# Mouse_Receive_SCH.net
KiCad netlist of a schematic drawn in Altium Designer
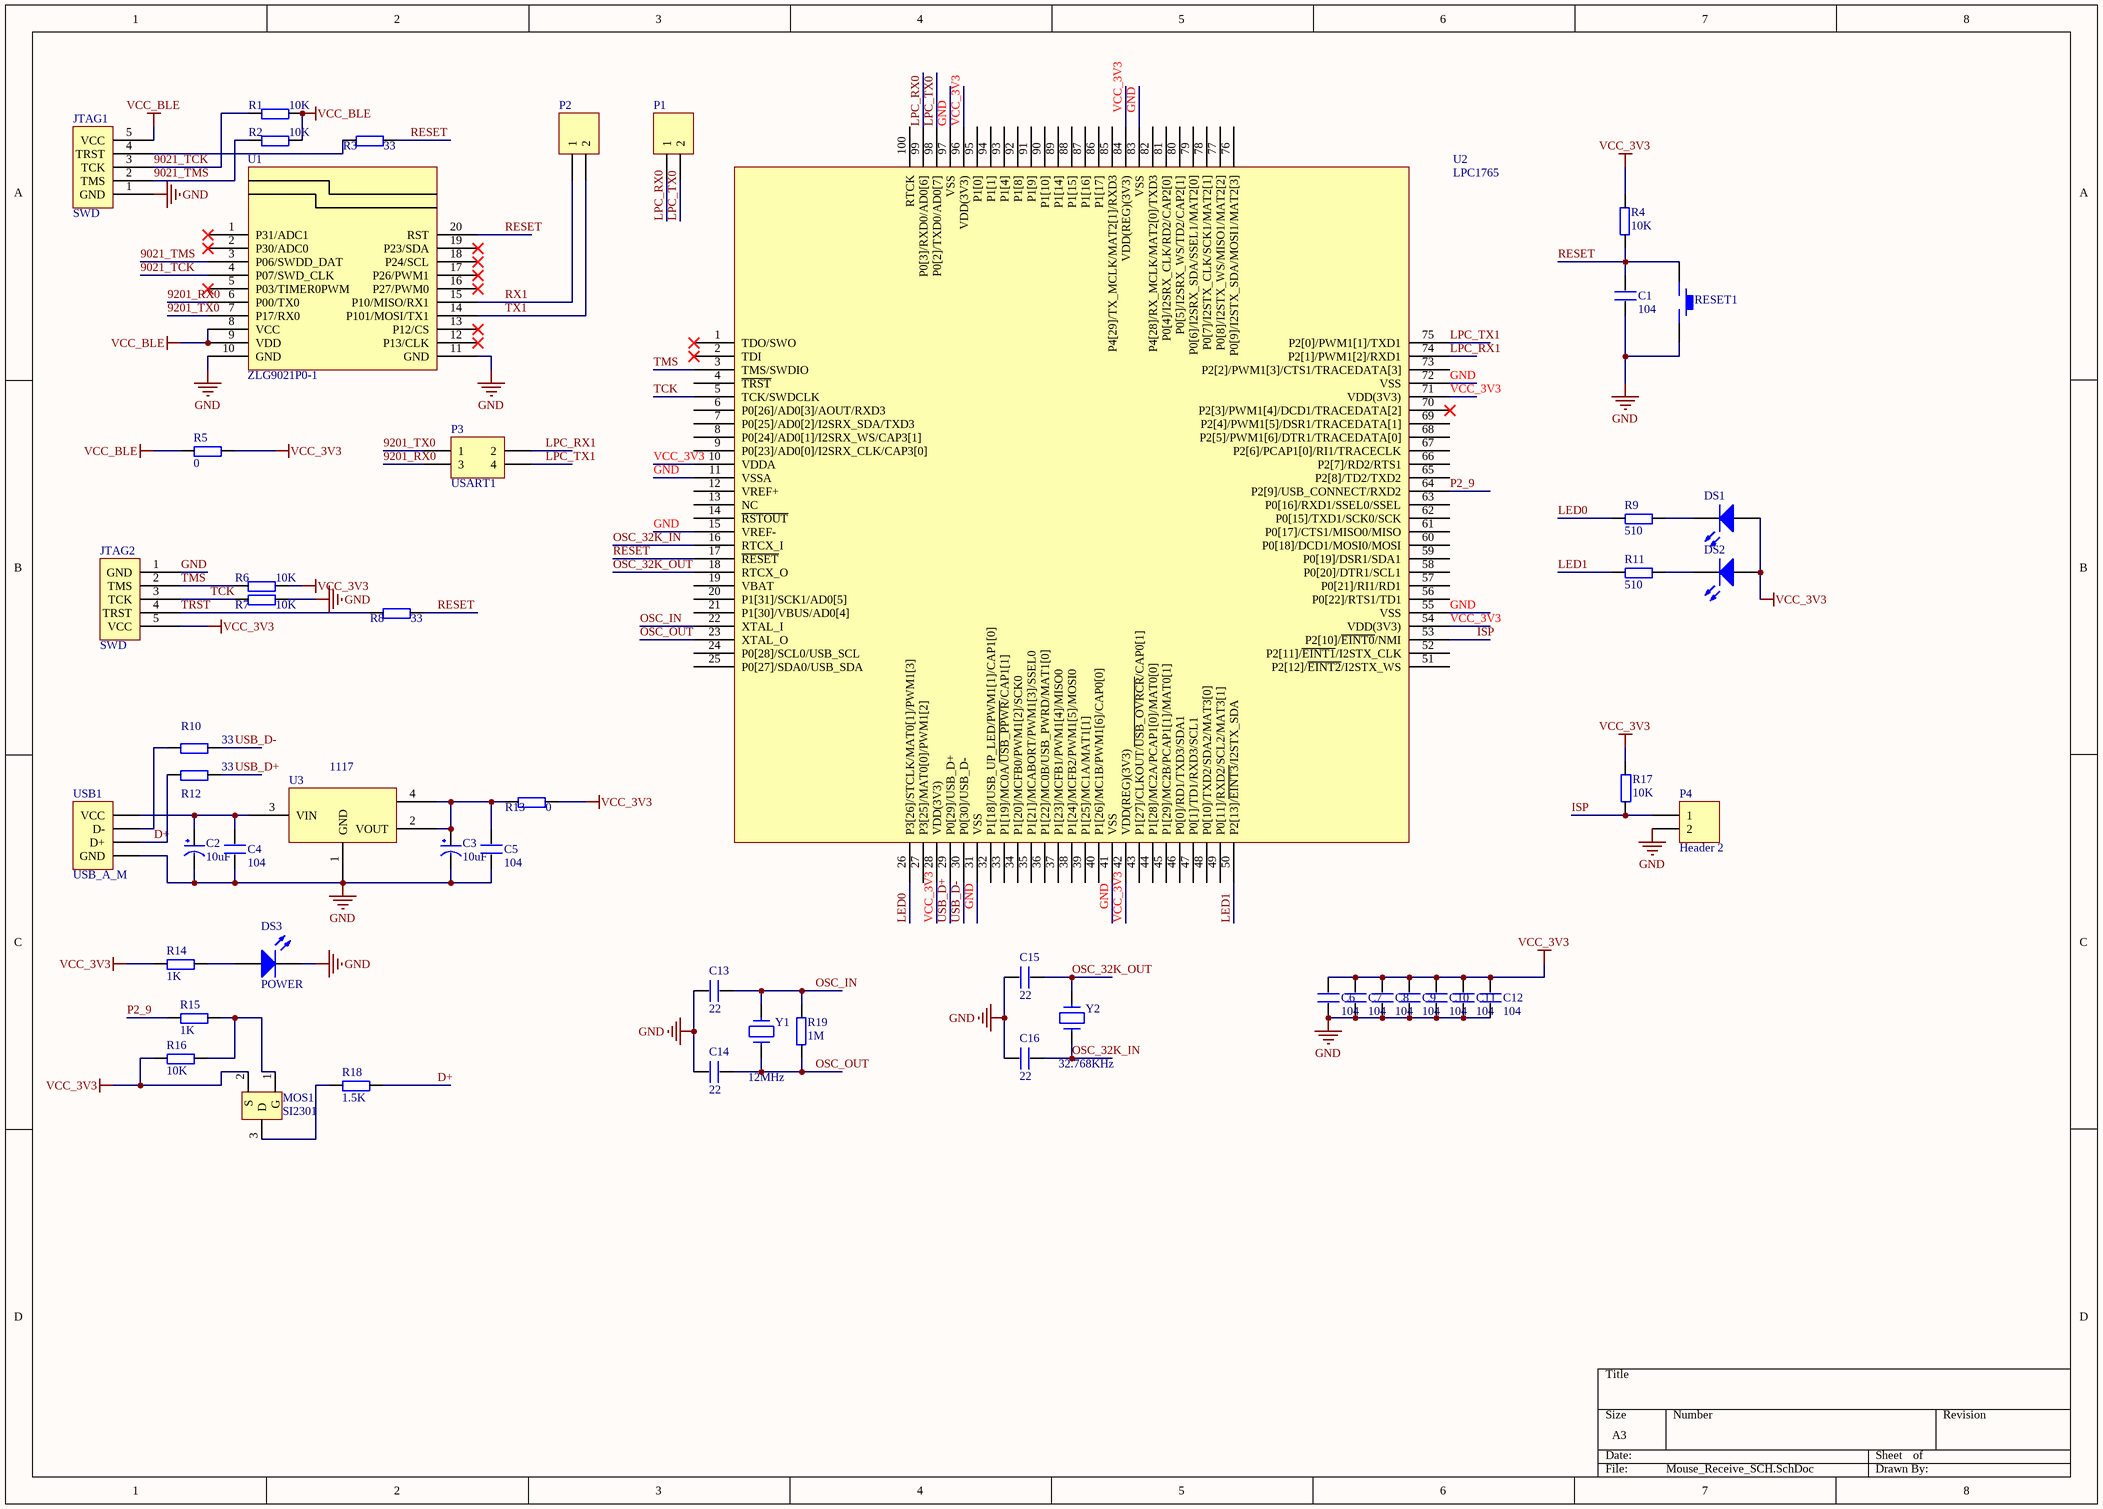
[diagram p0: Mouse_Receive_SCH.SchDoc]

(export (version "E")
  (design (tool "Eeschema 10.0.6"))
  (components
    (comp (ref "C1") (value "104") (footprint "0603P") (libsource (lib "MY_SCH_Lib") (part "C")))
    (comp (ref "C2") (value "10uF") (footprint "TAJ_A") (libsource (lib "MY_SCH_Lib") (part "CAP")))
    (comp (ref "C3") (value "10uF") (footprint "TAJ_A") (libsource (lib "MY_SCH_Lib") (part "CAP")))
    (comp (ref "C4") (value "104") (footprint "0603P") (libsource (lib "MY_SCH_Lib") (part "C")))
    (comp (ref "C5") (value "104") (footprint "0603P") (libsource (lib "MY_SCH_Lib") (part "C")))
    (comp (ref "C6") (value "104") (footprint "0603P") (libsource (lib "MY_SCH_Lib") (part "C")))
    (comp (ref "C7") (value "104") (footprint "0603P") (libsource (lib "MY_SCH_Lib") (part "C")))
    (comp (ref "C8") (value "104") (footprint "0603P") (libsource (lib "MY_SCH_Lib") (part "C")))
    (comp (ref "C9") (value "104") (footprint "0603P") (libsource (lib "MY_SCH_Lib") (part "C")))
    (comp (ref "C10") (value "104") (footprint "0603P") (libsource (lib "MY_SCH_Lib") (part "C")))
    (comp (ref "C11") (value "104") (footprint "0603P") (libsource (lib "MY_SCH_Lib") (part "C")))
    (comp (ref "C12") (value "104") (footprint "0603P") (libsource (lib "MY_SCH_Lib") (part "C")))
    (comp (ref "C13") (value "22") (footprint "0603P") (libsource (lib "MY_SCH_Lib") (part "C")))
    (comp (ref "C14") (value "22") (footprint "0603P") (libsource (lib "MY_SCH_Lib") (part "C")))
    (comp (ref "C15") (value "22") (footprint "0603P") (libsource (lib "MY_SCH_Lib") (part "C")))
    (comp (ref "C16") (value "22") (footprint "0603P") (libsource (lib "MY_SCH_Lib") (part "C")))
    (comp (ref "DS1")
      (value "~")
      (footprint "SMDLED")
      (description "Typical RED, GREEN, YELLOW, AMBER GaAs LED")
      (fields (field (name "PUBLISHER") "Altium Limited"))
      (libsource (lib "MY_SCH_Lib") (part "LED2"))
    )
    (comp (ref "DS2")
      (value "~")
      (footprint "SMDLED")
      (description "Typical RED, GREEN, YELLOW, AMBER GaAs LED")
      (fields (field (name "PUBLISHER") "Altium Limited"))
      (libsource (lib "MY_SCH_Lib") (part "LED2"))
    )
    (comp (ref "DS3")
      (value "POWER")
      (footprint "SMDLED")
      (description "Typical RED, GREEN, YELLOW, AMBER GaAs LED")
      (fields (field (name "PUBLISHER") "Altium Limited"))
      (libsource (lib "MY_SCH_Lib") (part "LED2"))
    )
    (comp (ref "JTAG1") (value "SWD") (footprint "HEAD5") (libsource (lib "") (part "SWD_1")))
    (comp (ref "JTAG2") (value "SWD") (footprint "HEAD5") (libsource (lib "MY_SCH_Lib") (part "SWD")))
    (comp (ref "MOS1")
      (value "SI2301")
      (footprint "SOT-23")
      (description "IRLML6401/SI2301")
      (libsource (lib "MY_SCH_Lib") (part "MOS-P"))
    )
    (comp (ref "P1")
      (value "~")
      (footprint "HDR1X2")
      (fields (field (name "PUBLISHER") "Altium Limited"))
      (libsource (lib "MY_SCH_Lib") (part "Header 2"))
    )
    (comp (ref "P2")
      (value "~")
      (footprint "HDR1X2")
      (fields (field (name "PUBLISHER") "Altium Limited"))
      (libsource (lib "MY_SCH_Lib") (part "Header 2"))
    )
    (comp (ref "P3")
      (value "USART1")
      (footprint "HDR2X2")
      (description "Header, 2-Pin, Dual row")
      (fields (field (name "PUBLISHER") "Altium Limited"))
      (libsource (lib "MY_SCH_Lib") (part "Header 2X2"))
    )
    (comp (ref "P4")
      (value "Header 2")
      (footprint "HDR1X2")
      (fields (field (name "PUBLISHER") "Altium Limited"))
      (libsource (lib "") (part "Header 2_1"))
    )
    (comp (ref "R1") (value "10K") (footprint "0603P") (libsource (lib "MY_SCH_Lib") (part "R")))
    (comp (ref "R2") (value "10K") (footprint "0603P") (libsource (lib "MY_SCH_Lib") (part "R")))
    (comp (ref "R3") (value "33") (footprint "0603P") (libsource (lib "MY_SCH_Lib") (part "R")))
    (comp (ref "R4") (value "10K") (footprint "0603P") (libsource (lib "MY_SCH_Lib") (part "R")))
    (comp (ref "R5") (value "0") (footprint "0603P") (libsource (lib "MY_SCH_Lib") (part "R")))
    (comp (ref "R6") (value "10K") (footprint "0603P") (libsource (lib "MY_SCH_Lib") (part "R")))
    (comp (ref "R7") (value "10K") (footprint "0603P") (libsource (lib "MY_SCH_Lib") (part "R")))
    (comp (ref "R8") (value "33") (footprint "0603P") (libsource (lib "MY_SCH_Lib") (part "R")))
    (comp (ref "R9") (value "510") (footprint "0603P") (libsource (lib "MY_SCH_Lib") (part "R")))
    (comp (ref "R10") (value "33") (footprint "0603P") (libsource (lib "MY_SCH_Lib") (part "R")))
    (comp (ref "R11") (value "510") (footprint "0603P") (libsource (lib "MY_SCH_Lib") (part "R")))
    (comp (ref "R12") (value "33") (footprint "0603P") (libsource (lib "MY_SCH_Lib") (part "R")))
    (comp (ref "R13") (value "0") (footprint "0603P") (libsource (lib "MY_SCH_Lib") (part "R")))
    (comp (ref "R14") (value "1K") (footprint "0603P") (libsource (lib "MY_SCH_Lib") (part "R")))
    (comp (ref "R15") (value "1K") (footprint "0603P") (libsource (lib "MY_SCH_Lib") (part "R")))
    (comp (ref "R16") (value "10K") (footprint "0603P") (libsource (lib "MY_SCH_Lib") (part "R")))
    (comp (ref "R17") (value "10K") (footprint "0603P") (libsource (lib "MY_SCH_Lib") (part "R")))
    (comp (ref "R18") (value "1.5K") (footprint "0603P") (libsource (lib "MY_SCH_Lib") (part "R")))
    (comp (ref "R19") (value "1M") (footprint "0603P") (libsource (lib "MY_SCH_Lib") (part "R")))
    (comp (ref "RESET1") (value "KEY_M") (footprint "KEY2") (libsource (lib "MY_SCH_Lib") (part "KEY_M")))
    (comp (ref "U1")
      (value "ZLG9021P0-1")
      (footprint "ZLG9021P0-1")
      (libsource (lib "MY_SCH_Lib") (part "ZLG9021P0-1"))
    )
    (comp (ref "U2")
      (value "LPC1765")
      (footprint "TQFP-100")
      (libsource (lib "LPC17xx_System_Sch_AD") (part "LPC1765"))
    )
    (comp (ref "U3") (value "1117") (footprint "AMS1117") (libsource (lib "MY_SCH_Lib") (part "1117")))
    (comp (ref "USB1")
      (value "USB_A_M")
      (footprint "USB-4-A-SMT-A")
      (libsource (lib "MY_SCH_Lib") (part "USB_A_M"))
    )
    (comp (ref "Y1")
      (value "12MHz")
      (footprint "8M")
      (description "Crystal")
      (libsource (lib "LPC17xx_System_Sch_AD") (part "CRYSTAL"))
    )
    (comp (ref "Y2")
      (value "32.768KHz")
      (footprint "CRY-32")
      (description "Crystal")
      (libsource (lib "LPC17xx_System_Sch_AD") (part "CRYSTAL"))
    )
  )
  (nets
    (net (code "1") (name "/9021_TCK") (class "Default")
      (node (ref "JTAG1") (pin "3") (pinfunction "TCK_3") (pintype "passive"))
      (node (ref "R1") (pin "1") (pintype "passive"))
      (node (ref "U1") (pin "4") (pinfunction "P07/SWD_CLK_4") (pintype "passive"))
    )
    (net (code "2") (name "/9021_TMS") (class "Default")
      (node (ref "JTAG1") (pin "2") (pinfunction "TMS_2") (pintype "passive"))
      (node (ref "R2") (pin "1") (pintype "passive"))
      (node (ref "U1") (pin "3") (pinfunction "P06/SWDD_DAT_3") (pintype "passive"))
    )
    (net (code "3") (name "/9201_RX0") (class "Default")
      (node (ref "P3") (pin "3") (pinfunction "3_3") (pintype "passive"))
      (node (ref "U1") (pin "6") (pinfunction "P00/TX0_6") (pintype "passive"))
    )
    (net (code "4") (name "/9201_TX0") (class "Default")
      (node (ref "P3") (pin "1") (pinfunction "1_1") (pintype "passive"))
      (node (ref "U1") (pin "7") (pinfunction "P17/RX0_7") (pintype "passive"))
    )
    (net (code "5") (name "/D+") (class "Default")
      (node (ref "R12") (pin "1") (pintype "passive"))
      (node (ref "R18") (pin "2") (pintype "passive"))
      (node (ref "USB1") (pin "3") (pinfunction "D+_3") (pintype "passive"))
    )
    (net (code "6") (name "/ISP") (class "Default")
      (node (ref "P4") (pin "1") (pinfunction "1_1") (pintype "passive"))
      (node (ref "R17") (pin "1") (pintype "passive"))
      (node (ref "U2") (pin "53") (pinfunction "P2[10]/~{EINT0}/NMI_53") (pintype "passive"))
    )
    (net (code "7") (name "/LED0") (class "Default")
      (node (ref "R9") (pin "1") (pintype "passive"))
      (node (ref "U2") (pin "26") (pinfunction "P3[26]/STCLK/MAT0[1]/PWM1[3]_26") (pintype "passive"))
    )
    (net (code "8") (name "/LED1") (class "Default")
      (node (ref "R11") (pin "1") (pintype "passive"))
      (node (ref "U2") (pin "50") (pinfunction "P2[13]/~{EINT3}/I2STX_SDA_50") (pintype "passive"))
    )
    (net (code "9") (name "/LPC_RX0") (class "Default")
      (node (ref "P1") (pin "1") (pinfunction "1_1") (pintype "passive"))
      (node (ref "U2") (pin "99") (pinfunction "P0[3]/RXD0/AD0[6]_99") (pintype "passive"))
    )
    (net (code "10") (name "/LPC_RX1") (class "Default")
      (node (ref "P3") (pin "2") (pinfunction "2_2") (pintype "passive"))
      (node (ref "U2") (pin "74") (pinfunction "P2[1]/PWM1[2]/RXD1_74") (pintype "passive"))
    )
    (net (code "11") (name "/LPC_TX0") (class "Default")
      (node (ref "P1") (pin "2") (pinfunction "2_2") (pintype "passive"))
      (node (ref "U2") (pin "98") (pinfunction "P0[2]/TXD0/AD0[7]_98") (pintype "passive"))
    )
    (net (code "12") (name "/LPC_TX1") (class "Default")
      (node (ref "P3") (pin "4") (pinfunction "4_4") (pintype "passive"))
      (node (ref "U2") (pin "75") (pinfunction "P2[0]/PWM1[1]/TXD1_75") (pintype "passive"))
    )
    (net (code "13") (name "/OSC_32K_IN") (class "Default")
      (node (ref "C16") (pin "2") (pintype "passive"))
      (node (ref "U2") (pin "16") (pinfunction "RTCX_I_16") (pintype "passive"))
      (node (ref "Y2") (pin "1") (pinfunction "1_1") (pintype "passive"))
    )
    (net (code "14") (name "/OSC_32K_OUT") (class "Default")
      (node (ref "C15") (pin "2") (pintype "passive"))
      (node (ref "U2") (pin "18") (pinfunction "RTCX_O_18") (pintype "passive"))
      (node (ref "Y2") (pin "2") (pinfunction "2_2") (pintype "passive"))
    )
    (net (code "15") (name "/OSC_IN") (class "Default")
      (node (ref "C13") (pin "2") (pintype "passive"))
      (node (ref "R19") (pin "1") (pintype "passive"))
      (node (ref "U2") (pin "22") (pinfunction "XTAL_I_22") (pintype "passive"))
      (node (ref "Y1") (pin "2") (pinfunction "2_2") (pintype "passive"))
    )
    (net (code "16") (name "/OSC_OUT") (class "Default")
      (node (ref "C14") (pin "2") (pintype "passive"))
      (node (ref "R19") (pin "2") (pintype "passive"))
      (node (ref "U2") (pin "23") (pinfunction "XTAL_O_23") (pintype "passive"))
      (node (ref "Y1") (pin "1") (pinfunction "1_1") (pintype "passive"))
    )
    (net (code "17") (name "/P2_9") (class "Default")
      (node (ref "R15") (pin "1") (pintype "passive"))
      (node (ref "U2") (pin "64") (pinfunction "P2[9]/USB_CONNECT/RXD2_64") (pintype "passive"))
    )
    (net (code "18") (name "/RESET") (class "Default")
      (node (ref "C1") (pin "2") (pintype "passive"))
      (node (ref "R3") (pin "2") (pintype "passive"))
      (node (ref "R4") (pin "1") (pintype "passive"))
      (node (ref "R8") (pin "2") (pintype "passive"))
      (node (ref "RESET1") (pin "2") (pinfunction "2_2") (pintype "passive"))
      (node (ref "U1") (pin "20") (pinfunction "RST_20") (pintype "passive"))
      (node (ref "U2") (pin "17") (pinfunction "~{RESET}_17") (pintype "passive"))
    )
    (net (code "19") (name "/RX1") (class "Default")
      (node (ref "P2") (pin "1") (pinfunction "1_1") (pintype "passive"))
      (node (ref "U1") (pin "15") (pinfunction "P10/MISO/RX1_15") (pintype "passive"))
    )
    (net (code "20") (name "/TCK") (class "Default")
      (node (ref "JTAG2") (pin "3") (pinfunction "TCK_3") (pintype "passive"))
      (node (ref "R7") (pin "1") (pintype "passive"))
      (node (ref "U2") (pin "5") (pinfunction "TCK/SWDCLK_5") (pintype "passive"))
    )
    (net (code "21") (name "/TMS") (class "Default")
      (node (ref "JTAG2") (pin "2") (pinfunction "TMS_2") (pintype "passive"))
      (node (ref "R6") (pin "1") (pintype "passive"))
      (node (ref "U2") (pin "3") (pinfunction "TMS/SWDIO_3") (pintype "passive"))
    )
    (net (code "22") (name "/TRST") (class "Default")
      (node (ref "JTAG2") (pin "4") (pinfunction "TRST_4") (pintype "passive"))
      (node (ref "R8") (pin "1") (pintype "passive"))
    )
    (net (code "23") (name "/TX1") (class "Default")
      (node (ref "P2") (pin "2") (pinfunction "2_2") (pintype "passive"))
      (node (ref "U1") (pin "14") (pinfunction "P101/MOSI/TX1_14") (pintype "passive"))
    )
    (net (code "24") (name "/USB_D+") (class "Default")
      (node (ref "R12") (pin "2") (pintype "passive"))
      (node (ref "U2") (pin "29") (pinfunction "P0[29]/USB_D+_29") (pintype "passive"))
    )
    (net (code "25") (name "/USB_D-") (class "Default")
      (node (ref "R10") (pin "2") (pintype "passive"))
      (node (ref "U2") (pin "30") (pinfunction "P0[30]/USB_D-_30") (pintype "passive"))
    )
    (net (code "26") (name "GND") (class "Default")
      (node (ref "C1") (pin "1") (pintype "passive"))
      (node (ref "C10") (pin "2") (pintype "passive"))
      (node (ref "C11") (pin "2") (pintype "passive"))
      (node (ref "C12") (pin "2") (pintype "passive"))
      (node (ref "C13") (pin "1") (pintype "passive"))
      (node (ref "C14") (pin "1") (pintype "passive"))
      (node (ref "C15") (pin "1") (pintype "passive"))
      (node (ref "C16") (pin "1") (pintype "passive"))
      (node (ref "C2") (pin "2") (pinfunction "GND_2") (pintype "passive"))
      (node (ref "C3") (pin "2") (pinfunction "GND_2") (pintype "passive"))
      (node (ref "C4") (pin "1") (pintype "passive"))
      (node (ref "C5") (pin "1") (pintype "passive"))
      (node (ref "C6") (pin "2") (pintype "passive"))
      (node (ref "C7") (pin "2") (pintype "passive"))
      (node (ref "C8") (pin "2") (pintype "passive"))
      (node (ref "C9") (pin "2") (pintype "passive"))
      (node (ref "DS3") (pin "2") (pinfunction "K_2") (pintype "passive"))
      (node (ref "JTAG1") (pin "1") (pinfunction "GND_1") (pintype "passive"))
      (node (ref "JTAG2") (pin "1") (pinfunction "GND_1") (pintype "passive"))
      (node (ref "P4") (pin "2") (pinfunction "2_2") (pintype "passive"))
      (node (ref "R7") (pin "2") (pintype "passive"))
      (node (ref "RESET1") (pin "1") (pinfunction "1_1") (pintype "passive"))
      (node (ref "U1") (pin "10") (pinfunction "GND_10") (pintype "passive"))
      (node (ref "U1") (pin "11") (pinfunction "GND_11") (pintype "passive"))
      (node (ref "U2") (pin "11") (pinfunction "VSSA_11") (pintype "passive"))
      (node (ref "U2") (pin "15") (pinfunction "VREF-_15") (pintype "passive"))
      (node (ref "U2") (pin "31") (pinfunction "VSS_31") (pintype "passive"))
      (node (ref "U2") (pin "41") (pinfunction "VSS_41") (pintype "passive"))
      (node (ref "U2") (pin "55") (pinfunction "VSS_55") (pintype "passive"))
      (node (ref "U2") (pin "72") (pinfunction "VSS_72") (pintype "passive"))
      (node (ref "U2") (pin "83") (pinfunction "VSS_83") (pintype "passive"))
      (node (ref "U2") (pin "97") (pinfunction "VSS_97") (pintype "passive"))
      (node (ref "U3") (pin "1") (pinfunction "GND_1") (pintype "passive"))
      (node (ref "USB1") (pin "4") (pinfunction "GND_4") (pintype "passive"))
    )
    (net (code "27") (name "Net-(C2-VCC)") (class "Default")
      (node (ref "C2") (pin "1") (pinfunction "VCC_1") (pintype "passive"))
      (node (ref "C4") (pin "2") (pintype "passive"))
      (node (ref "U3") (pin "3") (pinfunction "VIN_3") (pintype "passive"))
      (node (ref "USB1") (pin "1") (pinfunction "VCC_1") (pintype "passive"))
    )
    (net (code "28") (name "Net-(C3-VCC)") (class "Default")
      (node (ref "C3") (pin "1") (pinfunction "VCC_1") (pintype "passive"))
      (node (ref "C5") (pin "2") (pintype "passive"))
      (node (ref "R13") (pin "1") (pintype "passive"))
      (node (ref "U3") (pin "2") (pinfunction "VOUT_2") (pintype "passive"))
      (node (ref "U3") (pin "4") (pinfunction "4_4") (pintype "passive"))
    )
    (net (code "29") (name "Net-(DS1-K)") (class "Default")
      (node (ref "DS1") (pin "2") (pinfunction "K_2") (pintype "passive"))
      (node (ref "R9") (pin "2") (pintype "passive"))
    )
    (net (code "30") (name "Net-(DS2-K)") (class "Default")
      (node (ref "DS2") (pin "2") (pinfunction "K_2") (pintype "passive"))
      (node (ref "R11") (pin "2") (pintype "passive"))
    )
    (net (code "31") (name "Net-(DS3-A)") (class "Default")
      (node (ref "DS3") (pin "1") (pinfunction "A_1") (pintype "passive"))
      (node (ref "R14") (pin "2") (pintype "passive"))
    )
    (net (code "32") (name "Net-(JTAG1-TRST)") (class "Default")
      (node (ref "JTAG1") (pin "4") (pinfunction "TRST_4") (pintype "passive"))
      (node (ref "R3") (pin "1") (pintype "passive"))
    )
    (net (code "33") (name "Net-(MOS1-D)") (class "Default")
      (node (ref "MOS1") (pin "3") (pinfunction "D_3") (pintype "passive"))
      (node (ref "R18") (pin "1") (pintype "passive"))
    )
    (net (code "34") (name "Net-(MOS1-G)") (class "Default")
      (node (ref "MOS1") (pin "1") (pinfunction "G_1") (pintype "passive"))
      (node (ref "R15") (pin "2") (pintype "passive"))
      (node (ref "R16") (pin "2") (pintype "passive"))
    )
    (net (code "35") (name "Net-(USB1-D-)") (class "Default")
      (node (ref "R10") (pin "1") (pintype "passive"))
      (node (ref "USB1") (pin "2") (pinfunction "D-_2") (pintype "passive"))
    )
    (net (code "36") (name "VCC_3V3") (class "Default")
      (node (ref "C10") (pin "1") (pintype "passive"))
      (node (ref "C11") (pin "1") (pintype "passive"))
      (node (ref "C12") (pin "1") (pintype "passive"))
      (node (ref "C6") (pin "1") (pintype "passive"))
      (node (ref "C7") (pin "1") (pintype "passive"))
      (node (ref "C8") (pin "1") (pintype "passive"))
      (node (ref "C9") (pin "1") (pintype "passive"))
      (node (ref "DS1") (pin "1") (pinfunction "A_1") (pintype "passive"))
      (node (ref "DS2") (pin "1") (pinfunction "A_1") (pintype "passive"))
      (node (ref "JTAG2") (pin "5") (pinfunction "VCC_5") (pintype "passive"))
      (node (ref "MOS1") (pin "2") (pinfunction "S_2") (pintype "passive"))
      (node (ref "R13") (pin "2") (pintype "passive"))
      (node (ref "R14") (pin "1") (pintype "passive"))
      (node (ref "R16") (pin "1") (pintype "passive"))
      (node (ref "R17") (pin "2") (pintype "passive"))
      (node (ref "R4") (pin "2") (pintype "passive"))
      (node (ref "R5") (pin "2") (pintype "passive"))
      (node (ref "R6") (pin "2") (pintype "passive"))
      (node (ref "U2") (pin "10") (pinfunction "VDDA_10") (pintype "passive"))
      (node (ref "U2") (pin "28") (pinfunction "VDD(3V3)_28") (pintype "passive"))
      (node (ref "U2") (pin "42") (pinfunction "VDD(REG)(3V3)_42") (pintype "passive"))
      (node (ref "U2") (pin "54") (pinfunction "VDD(3V3)_54") (pintype "passive"))
      (node (ref "U2") (pin "71") (pinfunction "VDD(3V3)_71") (pintype "passive"))
      (node (ref "U2") (pin "84") (pinfunction "VDD(REG)(3V3)_84") (pintype "passive"))
      (node (ref "U2") (pin "96") (pinfunction "VDD(3V3)_96") (pintype "passive"))
    )
    (net (code "37") (name "VCC_BLE") (class "Default")
      (node (ref "JTAG1") (pin "5") (pinfunction "VCC_5") (pintype "passive"))
      (node (ref "R1") (pin "2") (pintype "passive"))
      (node (ref "R2") (pin "2") (pintype "passive"))
      (node (ref "R5") (pin "1") (pintype "passive"))
      (node (ref "U1") (pin "8") (pinfunction "VCC_8") (pintype "passive"))
      (node (ref "U1") (pin "9") (pinfunction "VDD_9") (pintype "passive"))
    )
    (net (code "38") (name "unconnected-(U1-P03{slash}TIMER0PWM-Pad5)") (class "Default")
      (node (ref "U1") (pin "5") (pinfunction "P03/TIMER0PWM_5") (pintype "passive+no_connect"))
    )
    (net (code "39") (name "unconnected-(U1-P12{slash}CS-Pad13)") (class "Default")
      (node (ref "U1") (pin "13") (pinfunction "P12/CS_13") (pintype "passive+no_connect"))
    )
    (net (code "40") (name "unconnected-(U1-P13{slash}CLK-Pad12)") (class "Default")
      (node (ref "U1") (pin "12") (pinfunction "P13/CLK_12") (pintype "passive+no_connect"))
    )
    (net (code "41") (name "unconnected-(U1-P23{slash}SDA-Pad19)") (class "Default")
      (node (ref "U1") (pin "19") (pinfunction "P23/SDA_19") (pintype "passive+no_connect"))
    )
    (net (code "42") (name "unconnected-(U1-P24{slash}SCL-Pad18)") (class "Default")
      (node (ref "U1") (pin "18") (pinfunction "P24/SCL_18") (pintype "passive+no_connect"))
    )
    (net (code "43") (name "unconnected-(U1-P26{slash}PWM1-Pad17)") (class "Default")
      (node (ref "U1") (pin "17") (pinfunction "P26/PWM1_17") (pintype "passive+no_connect"))
    )
    (net (code "44") (name "unconnected-(U1-P27{slash}PWM0-Pad16)") (class "Default")
      (node (ref "U1") (pin "16") (pinfunction "P27/PWM0_16") (pintype "passive+no_connect"))
    )
    (net (code "45") (name "unconnected-(U1-P30{slash}ADC0-Pad2)") (class "Default")
      (node (ref "U1") (pin "2") (pinfunction "P30/ADC0_2") (pintype "passive+no_connect"))
    )
    (net (code "46") (name "unconnected-(U1-P31{slash}ADC1-Pad1)") (class "Default")
      (node (ref "U1") (pin "1") (pinfunction "P31/ADC1_1") (pintype "passive+no_connect"))
    )
    (net (code "47") (name "unconnected-(U2-NC-Pad13)") (class "Default")
      (node (ref "U2") (pin "13") (pinfunction "NC_13") (pintype "passive"))
    )
    (net (code "48") (name "unconnected-(U2-P0[0]{slash}RD1{slash}TXD3{slash}SDA1-Pad46)") (class "Default")
      (node (ref "U2") (pin "46") (pinfunction "P0[0]/RD1/TXD3/SDA1_46") (pintype "passive"))
    )
    (net (code "49") (name "unconnected-(U2-P0[1]{slash}TD1{slash}RXD3{slash}SCL1-Pad47)") (class "Default")
      (node (ref "U2") (pin "47") (pinfunction "P0[1]/TD1/RXD3/SCL1_47") (pintype "passive"))
    )
    (net (code "50") (name "unconnected-(U2-P0[4]{slash}I2SRX_CLK{slash}RD2{slash}CAP2[0]-Pad81)") (class "Default")
      (node (ref "U2") (pin "81") (pinfunction "P0[4]/I2SRX_CLK/RD2/CAP2[0]_81") (pintype "passive"))
    )
    (net (code "51") (name "unconnected-(U2-P0[5]{slash}I2SRX_WS{slash}TD2{slash}CAP2[1]-Pad80)") (class "Default")
      (node (ref "U2") (pin "80") (pinfunction "P0[5]/I2SRX_WS/TD2/CAP2[1]_80") (pintype "passive"))
    )
    (net (code "52") (name "unconnected-(U2-P0[6]{slash}I2SRX_SDA{slash}SSEL1{slash}MAT2[0]-Pad79)") (class "Default")
      (node (ref "U2") (pin "79") (pinfunction "P0[6]/I2SRX_SDA/SSEL1/MAT2[0]_79") (pintype "passive"))
    )
    (net (code "53") (name "unconnected-(U2-P0[7]{slash}I2STX_CLK{slash}SCK1{slash}MAT2[1]-Pad78)") (class "Default")
      (node (ref "U2") (pin "78") (pinfunction "P0[7]/I2STX_CLK/SCK1/MAT2[1]_78") (pintype "passive"))
    )
    (net (code "54") (name "unconnected-(U2-P0[8]{slash}I2STX_WS{slash}MISO1{slash}MAT2[2]-Pad77)") (class "Default")
      (node (ref "U2") (pin "77") (pinfunction "P0[8]/I2STX_WS/MISO1/MAT2[2]_77") (pintype "passive"))
    )
    (net (code "55") (name "unconnected-(U2-P0[9]{slash}I2STX_SDA{slash}MOSI1{slash}MAT2[3]-Pad76)") (class "Default")
      (node (ref "U2") (pin "76") (pinfunction "P0[9]/I2STX_SDA/MOSI1/MAT2[3]_76") (pintype "passive"))
    )
    (net (code "56") (name "unconnected-(U2-P0[10]{slash}TXD2{slash}SDA2{slash}MAT3[0]-Pad48)") (class "Default")
      (node (ref "U2") (pin "48") (pinfunction "P0[10]/TXD2/SDA2/MAT3[0]_48") (pintype "passive"))
    )
    (net (code "57") (name "unconnected-(U2-P0[11]{slash}RXD2{slash}SCL2{slash}MAT3[1]-Pad49)") (class "Default")
      (node (ref "U2") (pin "49") (pinfunction "P0[11]/RXD2/SCL2/MAT3[1]_49") (pintype "passive"))
    )
    (net (code "58") (name "unconnected-(U2-P0[15]{slash}TXD1{slash}SCK0{slash}SCK-Pad62)") (class "Default")
      (node (ref "U2") (pin "62") (pinfunction "P0[15]/TXD1/SCK0/SCK_62") (pintype "passive"))
    )
    (net (code "59") (name "unconnected-(U2-P0[16]{slash}RXD1{slash}SSEL0{slash}SSEL-Pad63)") (class "Default")
      (node (ref "U2") (pin "63") (pinfunction "P0[16]/RXD1/SSEL0/SSEL_63") (pintype "passive"))
    )
    (net (code "60") (name "unconnected-(U2-P0[17]{slash}CTS1{slash}MISO0{slash}MISO-Pad61)") (class "Default")
      (node (ref "U2") (pin "61") (pinfunction "P0[17]/CTS1/MISO0/MISO_61") (pintype "passive"))
    )
    (net (code "61") (name "unconnected-(U2-P0[18]{slash}DCD1{slash}MOSI0{slash}MOSI-Pad60)") (class "Default")
      (node (ref "U2") (pin "60") (pinfunction "P0[18]/DCD1/MOSI0/MOSI_60") (pintype "passive"))
    )
    (net (code "62") (name "unconnected-(U2-P0[19]{slash}DSR1{slash}SDA1-Pad59)") (class "Default")
      (node (ref "U2") (pin "59") (pinfunction "P0[19]/DSR1/SDA1_59") (pintype "passive"))
    )
    (net (code "63") (name "unconnected-(U2-P0[20]{slash}DTR1{slash}SCL1-Pad58)") (class "Default")
      (node (ref "U2") (pin "58") (pinfunction "P0[20]/DTR1/SCL1_58") (pintype "passive"))
    )
    (net (code "64") (name "unconnected-(U2-P0[21]{slash}RI1{slash}RD1-Pad57)") (class "Default")
      (node (ref "U2") (pin "57") (pinfunction "P0[21]/RI1/RD1_57") (pintype "passive"))
    )
    (net (code "65") (name "unconnected-(U2-P0[22]{slash}RTS1{slash}TD1-Pad56)") (class "Default")
      (node (ref "U2") (pin "56") (pinfunction "P0[22]/RTS1/TD1_56") (pintype "passive"))
    )
    (net (code "66") (name "unconnected-(U2-P0[23]{slash}AD0[0]{slash}I2SRX_CLK{slash}CAP3[0]-Pad9)") (class "Default")
      (node (ref "U2") (pin "9") (pinfunction "P0[23]/AD0[0]/I2SRX_CLK/CAP3[0]_9") (pintype "passive"))
    )
    (net (code "67") (name "unconnected-(U2-P0[24]{slash}AD0[1]{slash}I2SRX_WS{slash}CAP3[1]-Pad8)") (class "Default")
      (node (ref "U2") (pin "8") (pinfunction "P0[24]/AD0[1]/I2SRX_WS/CAP3[1]_8") (pintype "passive"))
    )
    (net (code "68") (name "unconnected-(U2-P0[25]{slash}AD0[2]{slash}I2SRX_SDA{slash}TXD3-Pad7)") (class "Default")
      (node (ref "U2") (pin "7") (pinfunction "P0[25]/AD0[2]/I2SRX_SDA/TXD3_7") (pintype "passive"))
    )
    (net (code "69") (name "unconnected-(U2-P0[26]{slash}AD0[3]{slash}AOUT{slash}RXD3-Pad6)") (class "Default")
      (node (ref "U2") (pin "6") (pinfunction "P0[26]/AD0[3]/AOUT/RXD3_6") (pintype "passive"))
    )
    (net (code "70") (name "unconnected-(U2-P0[27]{slash}SDA0{slash}USB_SDA-Pad25)") (class "Default")
      (node (ref "U2") (pin "25") (pinfunction "P0[27]/SDA0/USB_SDA_25") (pintype "passive"))
    )
    (net (code "71") (name "unconnected-(U2-P0[28]{slash}SCL0{slash}USB_SCL-Pad24)") (class "Default")
      (node (ref "U2") (pin "24") (pinfunction "P0[28]/SCL0/USB_SCL_24") (pintype "passive"))
    )
    (net (code "72") (name "unconnected-(U2-P1[0]-Pad95)") (class "Default")
      (node (ref "U2") (pin "95") (pinfunction "P1[0]_95") (pintype "passive"))
    )
    (net (code "73") (name "unconnected-(U2-P1[1]-Pad94)") (class "Default")
      (node (ref "U2") (pin "94") (pinfunction "P1[1]_94") (pintype "passive"))
    )
    (net (code "74") (name "unconnected-(U2-P1[4]-Pad93)") (class "Default")
      (node (ref "U2") (pin "93") (pinfunction "P1[4]_93") (pintype "passive"))
    )
    (net (code "75") (name "unconnected-(U2-P1[8]-Pad92)") (class "Default")
      (node (ref "U2") (pin "92") (pinfunction "P1[8]_92") (pintype "passive"))
    )
    (net (code "76") (name "unconnected-(U2-P1[9]-Pad91)") (class "Default")
      (node (ref "U2") (pin "91") (pinfunction "P1[9]_91") (pintype "passive"))
    )
    (net (code "77") (name "unconnected-(U2-P1[10]-Pad90)") (class "Default")
      (node (ref "U2") (pin "90") (pinfunction "P1[10]_90") (pintype "passive"))
    )
    (net (code "78") (name "unconnected-(U2-P1[14]-Pad89)") (class "Default")
      (node (ref "U2") (pin "89") (pinfunction "P1[14]_89") (pintype "passive"))
    )
    (net (code "79") (name "unconnected-(U2-P1[15]-Pad88)") (class "Default")
      (node (ref "U2") (pin "88") (pinfunction "P1[15]_88") (pintype "passive"))
    )
    (net (code "80") (name "unconnected-(U2-P1[16]-Pad87)") (class "Default")
      (node (ref "U2") (pin "87") (pinfunction "P1[16]_87") (pintype "passive"))
    )
    (net (code "81") (name "unconnected-(U2-P1[17]-Pad86)") (class "Default")
      (node (ref "U2") (pin "86") (pinfunction "P1[17]_86") (pintype "passive"))
    )
    (net (code "82") (name "unconnected-(U2-P1[18]{slash}USB_UP_LED{slash}PWM1[1]{slash}CAP1[0]-Pad32)") (class "Default")
      (node (ref "U2") (pin "32") (pinfunction "P1[18]/USB_UP_LED/PWM1[1]/CAP1[0]_32") (pintype "passive"))
    )
    (net (code "83") (name "unconnected-(U2-P1[19]{slash}MC0A{slash}~{USB_PPWR}{slash}CAP1[1]-Pad33)") (class "Default")
      (node (ref "U2") (pin "33") (pinfunction "P1[19]/MC0A/~{USB_PPWR}/CAP1[1]_33") (pintype "passive"))
    )
    (net (code "84") (name "unconnected-(U2-P1[20]{slash}MCFB0{slash}PWM1[2]{slash}SCK0-Pad34)") (class "Default")
      (node (ref "U2") (pin "34") (pinfunction "P1[20]/MCFB0/PWM1[2]/SCK0_34") (pintype "passive"))
    )
    (net (code "85") (name "unconnected-(U2-P1[21]{slash}MCABORT{slash}PWM1[3]{slash}SSEL0-Pad35)") (class "Default")
      (node (ref "U2") (pin "35") (pinfunction "P1[21]/MCABORT/PWM1[3]/SSEL0_35") (pintype "passive"))
    )
    (net (code "86") (name "unconnected-(U2-P1[22]{slash}MC0B{slash}USB_PWRD{slash}MAT1[0]-Pad36)") (class "Default")
      (node (ref "U2") (pin "36") (pinfunction "P1[22]/MC0B/USB_PWRD/MAT1[0]_36") (pintype "passive"))
    )
    (net (code "87") (name "unconnected-(U2-P1[23]{slash}MCFB1{slash}PWM1[4]{slash}MISO0-Pad37)") (class "Default")
      (node (ref "U2") (pin "37") (pinfunction "P1[23]/MCFB1/PWM1[4]/MISO0_37") (pintype "passive"))
    )
    (net (code "88") (name "unconnected-(U2-P1[24]{slash}MCFB2{slash}PWM1[5]{slash}MOSI0-Pad38)") (class "Default")
      (node (ref "U2") (pin "38") (pinfunction "P1[24]/MCFB2/PWM1[5]/MOSI0_38") (pintype "passive"))
    )
    (net (code "89") (name "unconnected-(U2-P1[25]{slash}MC1A{slash}MAT1[1]-Pad39)") (class "Default")
      (node (ref "U2") (pin "39") (pinfunction "P1[25]/MC1A/MAT1[1]_39") (pintype "passive"))
    )
    (net (code "90") (name "unconnected-(U2-P1[26]{slash}MC1B{slash}PWM1[6]{slash}CAP0[0]-Pad40)") (class "Default")
      (node (ref "U2") (pin "40") (pinfunction "P1[26]/MC1B/PWM1[6]/CAP0[0]_40") (pintype "passive"))
    )
    (net (code "91") (name "unconnected-(U2-P1[27]{slash}CLKOUT{slash}~{USB_OVRCR}{slash}CAP0[1]-Pad43)") (class "Default")
      (node (ref "U2") (pin "43") (pinfunction "P1[27]/CLKOUT/~{USB_OVRCR}/CAP0[1]_43") (pintype "passive"))
    )
    (net (code "92") (name "unconnected-(U2-P1[28]{slash}MC2A{slash}PCAP1[0]{slash}MAT0[0]-Pad44)") (class "Default")
      (node (ref "U2") (pin "44") (pinfunction "P1[28]/MC2A/PCAP1[0]/MAT0[0]_44") (pintype "passive"))
    )
    (net (code "93") (name "unconnected-(U2-P1[29]{slash}MC2B{slash}PCAP1[1]{slash}MAT0[1]-Pad45)") (class "Default")
      (node (ref "U2") (pin "45") (pinfunction "P1[29]/MC2B/PCAP1[1]/MAT0[1]_45") (pintype "passive"))
    )
    (net (code "94") (name "unconnected-(U2-P1[30]{slash}VBUS{slash}AD0[4]-Pad21)") (class "Default")
      (node (ref "U2") (pin "21") (pinfunction "P1[30]/VBUS/AD0[4]_21") (pintype "passive"))
    )
    (net (code "95") (name "unconnected-(U2-P1[31]{slash}SCK1{slash}AD0[5]-Pad20)") (class "Default")
      (node (ref "U2") (pin "20") (pinfunction "P1[31]/SCK1/AD0[5]_20") (pintype "passive"))
    )
    (net (code "96") (name "unconnected-(U2-P2[2]{slash}PWM1[3]{slash}CTS1{slash}TRACEDATA[3]-Pad73)") (class "Default")
      (node (ref "U2") (pin "73") (pinfunction "P2[2]/PWM1[3]/CTS1/TRACEDATA[3]_73") (pintype "passive"))
    )
    (net (code "97") (name "unconnected-(U2-P2[3]{slash}PWM1[4]{slash}DCD1{slash}TRACEDATA[2]-Pad70)") (class "Default")
      (node (ref "U2") (pin "70") (pinfunction "P2[3]/PWM1[4]/DCD1/TRACEDATA[2]_70") (pintype "passive+no_connect"))
    )
    (net (code "98") (name "unconnected-(U2-P2[4]{slash}PWM1[5]{slash}DSR1{slash}TRACEDATA[1]-Pad69)") (class "Default")
      (node (ref "U2") (pin "69") (pinfunction "P2[4]/PWM1[5]/DSR1/TRACEDATA[1]_69") (pintype "passive"))
    )
    (net (code "99") (name "unconnected-(U2-P2[5]{slash}PWM1[6]{slash}DTR1{slash}TRACEDATA[0]-Pad68)") (class "Default")
      (node (ref "U2") (pin "68") (pinfunction "P2[5]/PWM1[6]/DTR1/TRACEDATA[0]_68") (pintype "passive"))
    )
    (net (code "100") (name "unconnected-(U2-P2[6]{slash}PCAP1[0]{slash}RI1{slash}TRACECLK-Pad67)") (class "Default")
      (node (ref "U2") (pin "67") (pinfunction "P2[6]/PCAP1[0]/RI1/TRACECLK_67") (pintype "passive"))
    )
    (net (code "101") (name "unconnected-(U2-P2[7]{slash}RD2{slash}RTS1-Pad66)") (class "Default")
      (node (ref "U2") (pin "66") (pinfunction "P2[7]/RD2/RTS1_66") (pintype "passive"))
    )
    (net (code "102") (name "unconnected-(U2-P2[8]{slash}TD2{slash}TXD2-Pad65)") (class "Default")
      (node (ref "U2") (pin "65") (pinfunction "P2[8]/TD2/TXD2_65") (pintype "passive"))
    )
    (net (code "103") (name "unconnected-(U2-P2[11]{slash}~{EINT1}{slash}I2STX_CLK-Pad52)") (class "Default")
      (node (ref "U2") (pin "52") (pinfunction "P2[11]/~{EINT1}/I2STX_CLK_52") (pintype "passive"))
    )
    (net (code "104") (name "unconnected-(U2-P2[12]{slash}~{EINT2}{slash}I2STX_WS-Pad51)") (class "Default")
      (node (ref "U2") (pin "51") (pinfunction "P2[12]/~{EINT2}/I2STX_WS_51") (pintype "passive"))
    )
    (net (code "105") (name "unconnected-(U2-P3[25]{slash}MAT0[0]{slash}PWM1[2]-Pad27)") (class "Default")
      (node (ref "U2") (pin "27") (pinfunction "P3[25]/MAT0[0]/PWM1[2]_27") (pintype "passive"))
    )
    (net (code "106") (name "unconnected-(U2-P4[28]{slash}RX_MCLK{slash}MAT2[0]{slash}TXD3-Pad82)") (class "Default")
      (node (ref "U2") (pin "82") (pinfunction "P4[28]/RX_MCLK/MAT2[0]/TXD3_82") (pintype "passive"))
    )
    (net (code "107") (name "unconnected-(U2-P4[29]{slash}TX_MCLK{slash}MAT2[1]{slash}RXD3-Pad85)") (class "Default")
      (node (ref "U2") (pin "85") (pinfunction "P4[29]/TX_MCLK/MAT2[1]/RXD3_85") (pintype "passive"))
    )
    (net (code "108") (name "unconnected-(U2-RTCK-Pad100)") (class "Default")
      (node (ref "U2") (pin "100") (pinfunction "RTCK_100") (pintype "passive"))
    )
    (net (code "109") (name "unconnected-(U2-TDI-Pad2)") (class "Default")
      (node (ref "U2") (pin "2") (pinfunction "TDI_2") (pintype "passive+no_connect"))
    )
    (net (code "110") (name "unconnected-(U2-TDO{slash}SWO-Pad1)") (class "Default")
      (node (ref "U2") (pin "1") (pinfunction "TDO/SWO_1") (pintype "passive+no_connect"))
    )
    (net (code "111") (name "unconnected-(U2-VBAT-Pad19)") (class "Default")
      (node (ref "U2") (pin "19") (pinfunction "VBAT_19") (pintype "passive"))
    )
    (net (code "112") (name "unconnected-(U2-VREF+-Pad12)") (class "Default")
      (node (ref "U2") (pin "12") (pinfunction "VREF+_12") (pintype "passive"))
    )
    (net (code "113") (name "unconnected-(U2-~{RSTOUT}-Pad14)") (class "Default")
      (node (ref "U2") (pin "14") (pinfunction "~{RSTOUT}_14") (pintype "passive"))
    )
    (net (code "114") (name "unconnected-(U2-~{TRST}-Pad4)") (class "Default")
      (node (ref "U2") (pin "4") (pinfunction "~{TRST}_4") (pintype "passive"))
    )
  )
)
